# solderable_breadboard_mini.net
KiCad netlist of a schematic drawn in EAGLE
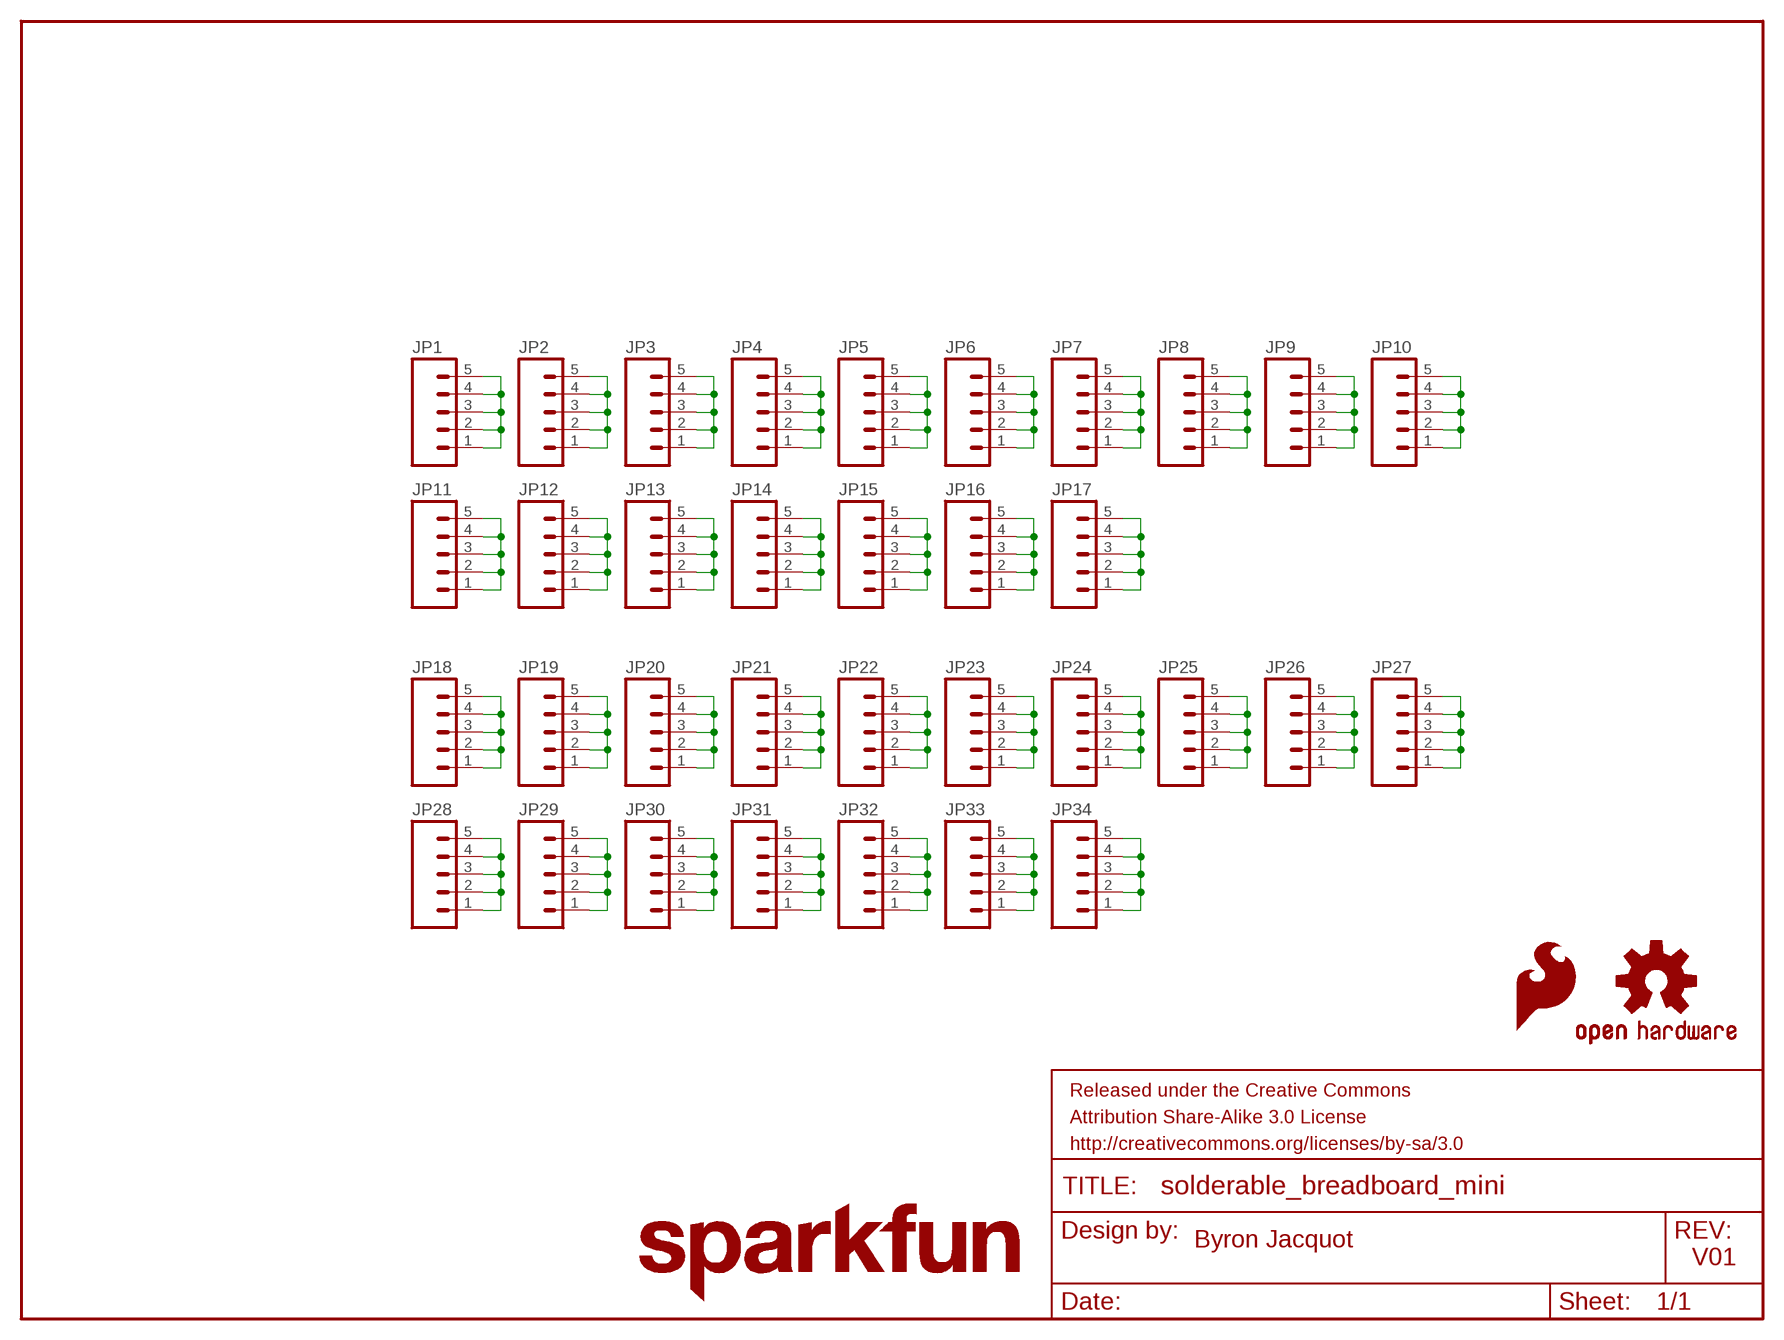
[diagram p0: schematic, sheet 1]

(export (version "E")
  (design (tool "Eeschema 10.0.6"))
  (components
    (comp (ref "FRAME1")
      (value "FRAME-LETTER")
      (footprint "eagle-import:CREATIVE_COMMONS")
      (libsource (lib "eagle-import") (part "FRAME-LETTER"))
    )
    (comp (ref "JP1")
      (value "M05NO_SILK")
      (footprint "eagle-import:1X05_NO_SILK")
      (libsource (lib "eagle-import") (part "M05NO_SILK"))
    )
    (comp (ref "JP2")
      (value "M05NO_SILK")
      (footprint "eagle-import:1X05_NO_SILK")
      (libsource (lib "eagle-import") (part "M05NO_SILK"))
    )
    (comp (ref "JP3")
      (value "M05NO_SILK")
      (footprint "eagle-import:1X05_NO_SILK")
      (libsource (lib "eagle-import") (part "M05NO_SILK"))
    )
    (comp (ref "JP4")
      (value "M05NO_SILK")
      (footprint "eagle-import:1X05_NO_SILK")
      (libsource (lib "eagle-import") (part "M05NO_SILK"))
    )
    (comp (ref "JP5")
      (value "M05NO_SILK")
      (footprint "eagle-import:1X05_NO_SILK")
      (libsource (lib "eagle-import") (part "M05NO_SILK"))
    )
    (comp (ref "JP6")
      (value "M05NO_SILK")
      (footprint "eagle-import:1X05_NO_SILK")
      (libsource (lib "eagle-import") (part "M05NO_SILK"))
    )
    (comp (ref "JP7")
      (value "M05NO_SILK")
      (footprint "eagle-import:1X05_NO_SILK")
      (libsource (lib "eagle-import") (part "M05NO_SILK"))
    )
    (comp (ref "JP8")
      (value "M05NO_SILK")
      (footprint "eagle-import:1X05_NO_SILK")
      (libsource (lib "eagle-import") (part "M05NO_SILK"))
    )
    (comp (ref "JP9")
      (value "M05NO_SILK")
      (footprint "eagle-import:1X05_NO_SILK")
      (libsource (lib "eagle-import") (part "M05NO_SILK"))
    )
    (comp (ref "JP10")
      (value "M05NO_SILK")
      (footprint "eagle-import:1X05_NO_SILK")
      (libsource (lib "eagle-import") (part "M05NO_SILK"))
    )
    (comp (ref "JP11")
      (value "M05NO_SILK")
      (footprint "eagle-import:1X05_NO_SILK")
      (libsource (lib "eagle-import") (part "M05NO_SILK"))
    )
    (comp (ref "JP12")
      (value "M05NO_SILK")
      (footprint "eagle-import:1X05_NO_SILK")
      (libsource (lib "eagle-import") (part "M05NO_SILK"))
    )
    (comp (ref "JP13")
      (value "M05NO_SILK")
      (footprint "eagle-import:1X05_NO_SILK")
      (libsource (lib "eagle-import") (part "M05NO_SILK"))
    )
    (comp (ref "JP14")
      (value "M05NO_SILK")
      (footprint "eagle-import:1X05_NO_SILK")
      (libsource (lib "eagle-import") (part "M05NO_SILK"))
    )
    (comp (ref "JP15")
      (value "M05NO_SILK")
      (footprint "eagle-import:1X05_NO_SILK")
      (libsource (lib "eagle-import") (part "M05NO_SILK"))
    )
    (comp (ref "JP16")
      (value "M05NO_SILK")
      (footprint "eagle-import:1X05_NO_SILK")
      (libsource (lib "eagle-import") (part "M05NO_SILK"))
    )
    (comp (ref "JP17")
      (value "M05NO_SILK")
      (footprint "eagle-import:1X05_NO_SILK")
      (libsource (lib "eagle-import") (part "M05NO_SILK"))
    )
    (comp (ref "JP18")
      (value "M05NO_SILK")
      (footprint "eagle-import:1X05_NO_SILK")
      (libsource (lib "eagle-import") (part "M05NO_SILK"))
    )
    (comp (ref "JP19")
      (value "M05NO_SILK")
      (footprint "eagle-import:1X05_NO_SILK")
      (libsource (lib "eagle-import") (part "M05NO_SILK"))
    )
    (comp (ref "JP20")
      (value "M05NO_SILK")
      (footprint "eagle-import:1X05_NO_SILK")
      (libsource (lib "eagle-import") (part "M05NO_SILK"))
    )
    (comp (ref "JP21")
      (value "M05NO_SILK")
      (footprint "eagle-import:1X05_NO_SILK")
      (libsource (lib "eagle-import") (part "M05NO_SILK"))
    )
    (comp (ref "JP22")
      (value "M05NO_SILK")
      (footprint "eagle-import:1X05_NO_SILK")
      (libsource (lib "eagle-import") (part "M05NO_SILK"))
    )
    (comp (ref "JP23")
      (value "M05NO_SILK")
      (footprint "eagle-import:1X05_NO_SILK")
      (libsource (lib "eagle-import") (part "M05NO_SILK"))
    )
    (comp (ref "JP24")
      (value "M05NO_SILK")
      (footprint "eagle-import:1X05_NO_SILK")
      (libsource (lib "eagle-import") (part "M05NO_SILK"))
    )
    (comp (ref "JP25")
      (value "M05NO_SILK")
      (footprint "eagle-import:1X05_NO_SILK")
      (libsource (lib "eagle-import") (part "M05NO_SILK"))
    )
    (comp (ref "JP26")
      (value "M05NO_SILK")
      (footprint "eagle-import:1X05_NO_SILK")
      (libsource (lib "eagle-import") (part "M05NO_SILK"))
    )
    (comp (ref "JP27")
      (value "M05NO_SILK")
      (footprint "eagle-import:1X05_NO_SILK")
      (libsource (lib "eagle-import") (part "M05NO_SILK"))
    )
    (comp (ref "JP28")
      (value "M05NO_SILK")
      (footprint "eagle-import:1X05_NO_SILK")
      (libsource (lib "eagle-import") (part "M05NO_SILK"))
    )
    (comp (ref "JP29")
      (value "M05NO_SILK")
      (footprint "eagle-import:1X05_NO_SILK")
      (libsource (lib "eagle-import") (part "M05NO_SILK"))
    )
    (comp (ref "JP30")
      (value "M05NO_SILK")
      (footprint "eagle-import:1X05_NO_SILK")
      (libsource (lib "eagle-import") (part "M05NO_SILK"))
    )
    (comp (ref "JP31")
      (value "M05NO_SILK")
      (footprint "eagle-import:1X05_NO_SILK")
      (libsource (lib "eagle-import") (part "M05NO_SILK"))
    )
    (comp (ref "JP32")
      (value "M05NO_SILK")
      (footprint "eagle-import:1X05_NO_SILK")
      (libsource (lib "eagle-import") (part "M05NO_SILK"))
    )
    (comp (ref "JP33")
      (value "M05NO_SILK")
      (footprint "eagle-import:1X05_NO_SILK")
      (libsource (lib "eagle-import") (part "M05NO_SILK"))
    )
    (comp (ref "JP34")
      (value "M05NO_SILK")
      (footprint "eagle-import:1X05_NO_SILK")
      (libsource (lib "eagle-import") (part "M05NO_SILK"))
    )
    (comp (ref "LOGO1")
      (value "SFE_LOGO_NAME.1_INCH")
      (footprint "eagle-import:SFE_LOGO_NAME_.1")
      (libsource (lib "eagle-import") (part "SFE_LOGO_NAME.1_INCH"))
    )
    (comp (ref "LOGO2")
      (value "OSHW-LOGOM")
      (footprint "eagle-import:OSHW-LOGO-M")
      (libsource (lib "eagle-import") (part "OSHW-LOGOM"))
    )
    (comp (ref "LOGO3")
      (value "SFE_LOGO_FLAME.1_INCH")
      (footprint "eagle-import:SFE_LOGO_FLAME_.1")
      (libsource (lib "eagle-import") (part "SFE_LOGO_FLAME.1_INCH"))
    )
    (comp (ref "LOGO4")
      (value "SFE_LOGO_FLAME.1_INCH")
      (footprint "eagle-import:SFE_LOGO_FLAME_.1")
      (libsource (lib "eagle-import") (part "SFE_LOGO_FLAME.1_INCH"))
    )
  )
  (nets
    (net (code "1") (name "Net-(JP1-Pad1)") (class "Default")
      (node (ref "JP1") (pin "1") (pinfunction "1_1") (pintype "passive"))
      (node (ref "JP1") (pin "2") (pinfunction "2_2") (pintype "passive"))
      (node (ref "JP1") (pin "3") (pinfunction "3_3") (pintype "passive"))
      (node (ref "JP1") (pin "4") (pinfunction "4_4") (pintype "passive"))
      (node (ref "JP1") (pin "5") (pinfunction "5_5") (pintype "passive"))
    )
    (net (code "2") (name "Net-(JP2-Pad1)") (class "Default")
      (node (ref "JP2") (pin "1") (pinfunction "1_1") (pintype "passive"))
      (node (ref "JP2") (pin "2") (pinfunction "2_2") (pintype "passive"))
      (node (ref "JP2") (pin "3") (pinfunction "3_3") (pintype "passive"))
      (node (ref "JP2") (pin "4") (pinfunction "4_4") (pintype "passive"))
      (node (ref "JP2") (pin "5") (pinfunction "5_5") (pintype "passive"))
    )
    (net (code "3") (name "Net-(JP3-Pad1)") (class "Default")
      (node (ref "JP3") (pin "1") (pinfunction "1_1") (pintype "passive"))
      (node (ref "JP3") (pin "2") (pinfunction "2_2") (pintype "passive"))
      (node (ref "JP3") (pin "3") (pinfunction "3_3") (pintype "passive"))
      (node (ref "JP3") (pin "4") (pinfunction "4_4") (pintype "passive"))
      (node (ref "JP3") (pin "5") (pinfunction "5_5") (pintype "passive"))
    )
    (net (code "4") (name "Net-(JP4-Pad1)") (class "Default")
      (node (ref "JP4") (pin "1") (pinfunction "1_1") (pintype "passive"))
      (node (ref "JP4") (pin "2") (pinfunction "2_2") (pintype "passive"))
      (node (ref "JP4") (pin "3") (pinfunction "3_3") (pintype "passive"))
      (node (ref "JP4") (pin "4") (pinfunction "4_4") (pintype "passive"))
      (node (ref "JP4") (pin "5") (pinfunction "5_5") (pintype "passive"))
    )
    (net (code "5") (name "Net-(JP5-Pad1)") (class "Default")
      (node (ref "JP5") (pin "1") (pinfunction "1_1") (pintype "passive"))
      (node (ref "JP5") (pin "2") (pinfunction "2_2") (pintype "passive"))
      (node (ref "JP5") (pin "3") (pinfunction "3_3") (pintype "passive"))
      (node (ref "JP5") (pin "4") (pinfunction "4_4") (pintype "passive"))
      (node (ref "JP5") (pin "5") (pinfunction "5_5") (pintype "passive"))
    )
    (net (code "6") (name "Net-(JP6-Pad1)") (class "Default")
      (node (ref "JP6") (pin "1") (pinfunction "1_1") (pintype "passive"))
      (node (ref "JP6") (pin "2") (pinfunction "2_2") (pintype "passive"))
      (node (ref "JP6") (pin "3") (pinfunction "3_3") (pintype "passive"))
      (node (ref "JP6") (pin "4") (pinfunction "4_4") (pintype "passive"))
      (node (ref "JP6") (pin "5") (pinfunction "5_5") (pintype "passive"))
    )
    (net (code "7") (name "Net-(JP7-Pad1)") (class "Default")
      (node (ref "JP7") (pin "1") (pinfunction "1_1") (pintype "passive"))
      (node (ref "JP7") (pin "2") (pinfunction "2_2") (pintype "passive"))
      (node (ref "JP7") (pin "3") (pinfunction "3_3") (pintype "passive"))
      (node (ref "JP7") (pin "4") (pinfunction "4_4") (pintype "passive"))
      (node (ref "JP7") (pin "5") (pinfunction "5_5") (pintype "passive"))
    )
    (net (code "8") (name "Net-(JP8-Pad1)") (class "Default")
      (node (ref "JP8") (pin "1") (pinfunction "1_1") (pintype "passive"))
      (node (ref "JP8") (pin "2") (pinfunction "2_2") (pintype "passive"))
      (node (ref "JP8") (pin "3") (pinfunction "3_3") (pintype "passive"))
      (node (ref "JP8") (pin "4") (pinfunction "4_4") (pintype "passive"))
      (node (ref "JP8") (pin "5") (pinfunction "5_5") (pintype "passive"))
    )
    (net (code "9") (name "Net-(JP9-Pad1)") (class "Default")
      (node (ref "JP9") (pin "1") (pinfunction "1_1") (pintype "passive"))
      (node (ref "JP9") (pin "2") (pinfunction "2_2") (pintype "passive"))
      (node (ref "JP9") (pin "3") (pinfunction "3_3") (pintype "passive"))
      (node (ref "JP9") (pin "4") (pinfunction "4_4") (pintype "passive"))
      (node (ref "JP9") (pin "5") (pinfunction "5_5") (pintype "passive"))
    )
    (net (code "10") (name "Net-(JP10-Pad1)") (class "Default")
      (node (ref "JP10") (pin "1") (pinfunction "1_1") (pintype "passive"))
      (node (ref "JP10") (pin "2") (pinfunction "2_2") (pintype "passive"))
      (node (ref "JP10") (pin "3") (pinfunction "3_3") (pintype "passive"))
      (node (ref "JP10") (pin "4") (pinfunction "4_4") (pintype "passive"))
      (node (ref "JP10") (pin "5") (pinfunction "5_5") (pintype "passive"))
    )
    (net (code "11") (name "Net-(JP11-Pad1)") (class "Default")
      (node (ref "JP11") (pin "1") (pinfunction "1_1") (pintype "passive"))
      (node (ref "JP11") (pin "2") (pinfunction "2_2") (pintype "passive"))
      (node (ref "JP11") (pin "3") (pinfunction "3_3") (pintype "passive"))
      (node (ref "JP11") (pin "4") (pinfunction "4_4") (pintype "passive"))
      (node (ref "JP11") (pin "5") (pinfunction "5_5") (pintype "passive"))
    )
    (net (code "12") (name "Net-(JP12-Pad1)") (class "Default")
      (node (ref "JP12") (pin "1") (pinfunction "1_1") (pintype "passive"))
      (node (ref "JP12") (pin "2") (pinfunction "2_2") (pintype "passive"))
      (node (ref "JP12") (pin "3") (pinfunction "3_3") (pintype "passive"))
      (node (ref "JP12") (pin "4") (pinfunction "4_4") (pintype "passive"))
      (node (ref "JP12") (pin "5") (pinfunction "5_5") (pintype "passive"))
    )
    (net (code "13") (name "Net-(JP13-Pad1)") (class "Default")
      (node (ref "JP13") (pin "1") (pinfunction "1_1") (pintype "passive"))
      (node (ref "JP13") (pin "2") (pinfunction "2_2") (pintype "passive"))
      (node (ref "JP13") (pin "3") (pinfunction "3_3") (pintype "passive"))
      (node (ref "JP13") (pin "4") (pinfunction "4_4") (pintype "passive"))
      (node (ref "JP13") (pin "5") (pinfunction "5_5") (pintype "passive"))
    )
    (net (code "14") (name "Net-(JP14-Pad1)") (class "Default")
      (node (ref "JP14") (pin "1") (pinfunction "1_1") (pintype "passive"))
      (node (ref "JP14") (pin "2") (pinfunction "2_2") (pintype "passive"))
      (node (ref "JP14") (pin "3") (pinfunction "3_3") (pintype "passive"))
      (node (ref "JP14") (pin "4") (pinfunction "4_4") (pintype "passive"))
      (node (ref "JP14") (pin "5") (pinfunction "5_5") (pintype "passive"))
    )
    (net (code "15") (name "Net-(JP15-Pad1)") (class "Default")
      (node (ref "JP15") (pin "1") (pinfunction "1_1") (pintype "passive"))
      (node (ref "JP15") (pin "2") (pinfunction "2_2") (pintype "passive"))
      (node (ref "JP15") (pin "3") (pinfunction "3_3") (pintype "passive"))
      (node (ref "JP15") (pin "4") (pinfunction "4_4") (pintype "passive"))
      (node (ref "JP15") (pin "5") (pinfunction "5_5") (pintype "passive"))
    )
    (net (code "16") (name "Net-(JP16-Pad1)") (class "Default")
      (node (ref "JP16") (pin "1") (pinfunction "1_1") (pintype "passive"))
      (node (ref "JP16") (pin "2") (pinfunction "2_2") (pintype "passive"))
      (node (ref "JP16") (pin "3") (pinfunction "3_3") (pintype "passive"))
      (node (ref "JP16") (pin "4") (pinfunction "4_4") (pintype "passive"))
      (node (ref "JP16") (pin "5") (pinfunction "5_5") (pintype "passive"))
    )
    (net (code "17") (name "Net-(JP17-Pad1)") (class "Default")
      (node (ref "JP17") (pin "1") (pinfunction "1_1") (pintype "passive"))
      (node (ref "JP17") (pin "2") (pinfunction "2_2") (pintype "passive"))
      (node (ref "JP17") (pin "3") (pinfunction "3_3") (pintype "passive"))
      (node (ref "JP17") (pin "4") (pinfunction "4_4") (pintype "passive"))
      (node (ref "JP17") (pin "5") (pinfunction "5_5") (pintype "passive"))
    )
    (net (code "18") (name "Net-(JP18-Pad1)") (class "Default")
      (node (ref "JP18") (pin "1") (pinfunction "1_1") (pintype "passive"))
      (node (ref "JP18") (pin "2") (pinfunction "2_2") (pintype "passive"))
      (node (ref "JP18") (pin "3") (pinfunction "3_3") (pintype "passive"))
      (node (ref "JP18") (pin "4") (pinfunction "4_4") (pintype "passive"))
      (node (ref "JP18") (pin "5") (pinfunction "5_5") (pintype "passive"))
    )
    (net (code "19") (name "Net-(JP19-Pad1)") (class "Default")
      (node (ref "JP19") (pin "1") (pinfunction "1_1") (pintype "passive"))
      (node (ref "JP19") (pin "2") (pinfunction "2_2") (pintype "passive"))
      (node (ref "JP19") (pin "3") (pinfunction "3_3") (pintype "passive"))
      (node (ref "JP19") (pin "4") (pinfunction "4_4") (pintype "passive"))
      (node (ref "JP19") (pin "5") (pinfunction "5_5") (pintype "passive"))
    )
    (net (code "20") (name "Net-(JP20-Pad1)") (class "Default")
      (node (ref "JP20") (pin "1") (pinfunction "1_1") (pintype "passive"))
      (node (ref "JP20") (pin "2") (pinfunction "2_2") (pintype "passive"))
      (node (ref "JP20") (pin "3") (pinfunction "3_3") (pintype "passive"))
      (node (ref "JP20") (pin "4") (pinfunction "4_4") (pintype "passive"))
      (node (ref "JP20") (pin "5") (pinfunction "5_5") (pintype "passive"))
    )
    (net (code "21") (name "Net-(JP21-Pad1)") (class "Default")
      (node (ref "JP21") (pin "1") (pinfunction "1_1") (pintype "passive"))
      (node (ref "JP21") (pin "2") (pinfunction "2_2") (pintype "passive"))
      (node (ref "JP21") (pin "3") (pinfunction "3_3") (pintype "passive"))
      (node (ref "JP21") (pin "4") (pinfunction "4_4") (pintype "passive"))
      (node (ref "JP21") (pin "5") (pinfunction "5_5") (pintype "passive"))
    )
    (net (code "22") (name "Net-(JP22-Pad1)") (class "Default")
      (node (ref "JP22") (pin "1") (pinfunction "1_1") (pintype "passive"))
      (node (ref "JP22") (pin "2") (pinfunction "2_2") (pintype "passive"))
      (node (ref "JP22") (pin "3") (pinfunction "3_3") (pintype "passive"))
      (node (ref "JP22") (pin "4") (pinfunction "4_4") (pintype "passive"))
      (node (ref "JP22") (pin "5") (pinfunction "5_5") (pintype "passive"))
    )
    (net (code "23") (name "Net-(JP23-Pad1)") (class "Default")
      (node (ref "JP23") (pin "1") (pinfunction "1_1") (pintype "passive"))
      (node (ref "JP23") (pin "2") (pinfunction "2_2") (pintype "passive"))
      (node (ref "JP23") (pin "3") (pinfunction "3_3") (pintype "passive"))
      (node (ref "JP23") (pin "4") (pinfunction "4_4") (pintype "passive"))
      (node (ref "JP23") (pin "5") (pinfunction "5_5") (pintype "passive"))
    )
    (net (code "24") (name "Net-(JP24-Pad1)") (class "Default")
      (node (ref "JP24") (pin "1") (pinfunction "1_1") (pintype "passive"))
      (node (ref "JP24") (pin "2") (pinfunction "2_2") (pintype "passive"))
      (node (ref "JP24") (pin "3") (pinfunction "3_3") (pintype "passive"))
      (node (ref "JP24") (pin "4") (pinfunction "4_4") (pintype "passive"))
      (node (ref "JP24") (pin "5") (pinfunction "5_5") (pintype "passive"))
    )
    (net (code "25") (name "Net-(JP25-Pad1)") (class "Default")
      (node (ref "JP25") (pin "1") (pinfunction "1_1") (pintype "passive"))
      (node (ref "JP25") (pin "2") (pinfunction "2_2") (pintype "passive"))
      (node (ref "JP25") (pin "3") (pinfunction "3_3") (pintype "passive"))
      (node (ref "JP25") (pin "4") (pinfunction "4_4") (pintype "passive"))
      (node (ref "JP25") (pin "5") (pinfunction "5_5") (pintype "passive"))
    )
    (net (code "26") (name "Net-(JP26-Pad1)") (class "Default")
      (node (ref "JP26") (pin "1") (pinfunction "1_1") (pintype "passive"))
      (node (ref "JP26") (pin "2") (pinfunction "2_2") (pintype "passive"))
      (node (ref "JP26") (pin "3") (pinfunction "3_3") (pintype "passive"))
      (node (ref "JP26") (pin "4") (pinfunction "4_4") (pintype "passive"))
      (node (ref "JP26") (pin "5") (pinfunction "5_5") (pintype "passive"))
    )
    (net (code "27") (name "Net-(JP27-Pad1)") (class "Default")
      (node (ref "JP27") (pin "1") (pinfunction "1_1") (pintype "passive"))
      (node (ref "JP27") (pin "2") (pinfunction "2_2") (pintype "passive"))
      (node (ref "JP27") (pin "3") (pinfunction "3_3") (pintype "passive"))
      (node (ref "JP27") (pin "4") (pinfunction "4_4") (pintype "passive"))
      (node (ref "JP27") (pin "5") (pinfunction "5_5") (pintype "passive"))
    )
    (net (code "28") (name "Net-(JP28-Pad1)") (class "Default")
      (node (ref "JP28") (pin "1") (pinfunction "1_1") (pintype "passive"))
      (node (ref "JP28") (pin "2") (pinfunction "2_2") (pintype "passive"))
      (node (ref "JP28") (pin "3") (pinfunction "3_3") (pintype "passive"))
      (node (ref "JP28") (pin "4") (pinfunction "4_4") (pintype "passive"))
      (node (ref "JP28") (pin "5") (pinfunction "5_5") (pintype "passive"))
    )
    (net (code "29") (name "Net-(JP29-Pad1)") (class "Default")
      (node (ref "JP29") (pin "1") (pinfunction "1_1") (pintype "passive"))
      (node (ref "JP29") (pin "2") (pinfunction "2_2") (pintype "passive"))
      (node (ref "JP29") (pin "3") (pinfunction "3_3") (pintype "passive"))
      (node (ref "JP29") (pin "4") (pinfunction "4_4") (pintype "passive"))
      (node (ref "JP29") (pin "5") (pinfunction "5_5") (pintype "passive"))
    )
    (net (code "30") (name "Net-(JP30-Pad1)") (class "Default")
      (node (ref "JP30") (pin "1") (pinfunction "1_1") (pintype "passive"))
      (node (ref "JP30") (pin "2") (pinfunction "2_2") (pintype "passive"))
      (node (ref "JP30") (pin "3") (pinfunction "3_3") (pintype "passive"))
      (node (ref "JP30") (pin "4") (pinfunction "4_4") (pintype "passive"))
      (node (ref "JP30") (pin "5") (pinfunction "5_5") (pintype "passive"))
    )
    (net (code "31") (name "Net-(JP31-Pad1)") (class "Default")
      (node (ref "JP31") (pin "1") (pinfunction "1_1") (pintype "passive"))
      (node (ref "JP31") (pin "2") (pinfunction "2_2") (pintype "passive"))
      (node (ref "JP31") (pin "3") (pinfunction "3_3") (pintype "passive"))
      (node (ref "JP31") (pin "4") (pinfunction "4_4") (pintype "passive"))
      (node (ref "JP31") (pin "5") (pinfunction "5_5") (pintype "passive"))
    )
    (net (code "32") (name "Net-(JP32-Pad1)") (class "Default")
      (node (ref "JP32") (pin "1") (pinfunction "1_1") (pintype "passive"))
      (node (ref "JP32") (pin "2") (pinfunction "2_2") (pintype "passive"))
      (node (ref "JP32") (pin "3") (pinfunction "3_3") (pintype "passive"))
      (node (ref "JP32") (pin "4") (pinfunction "4_4") (pintype "passive"))
      (node (ref "JP32") (pin "5") (pinfunction "5_5") (pintype "passive"))
    )
    (net (code "33") (name "Net-(JP33-Pad1)") (class "Default")
      (node (ref "JP33") (pin "1") (pinfunction "1_1") (pintype "passive"))
      (node (ref "JP33") (pin "2") (pinfunction "2_2") (pintype "passive"))
      (node (ref "JP33") (pin "3") (pinfunction "3_3") (pintype "passive"))
      (node (ref "JP33") (pin "4") (pinfunction "4_4") (pintype "passive"))
      (node (ref "JP33") (pin "5") (pinfunction "5_5") (pintype "passive"))
    )
    (net (code "34") (name "Net-(JP34-Pad1)") (class "Default")
      (node (ref "JP34") (pin "1") (pinfunction "1_1") (pintype "passive"))
      (node (ref "JP34") (pin "2") (pinfunction "2_2") (pintype "passive"))
      (node (ref "JP34") (pin "3") (pinfunction "3_3") (pintype "passive"))
      (node (ref "JP34") (pin "4") (pinfunction "4_4") (pintype "passive"))
      (node (ref "JP34") (pin "5") (pinfunction "5_5") (pintype "passive"))
    )
  )
)
